# schematic.net
KiCad netlist of a schematic drawn in EasyEDA
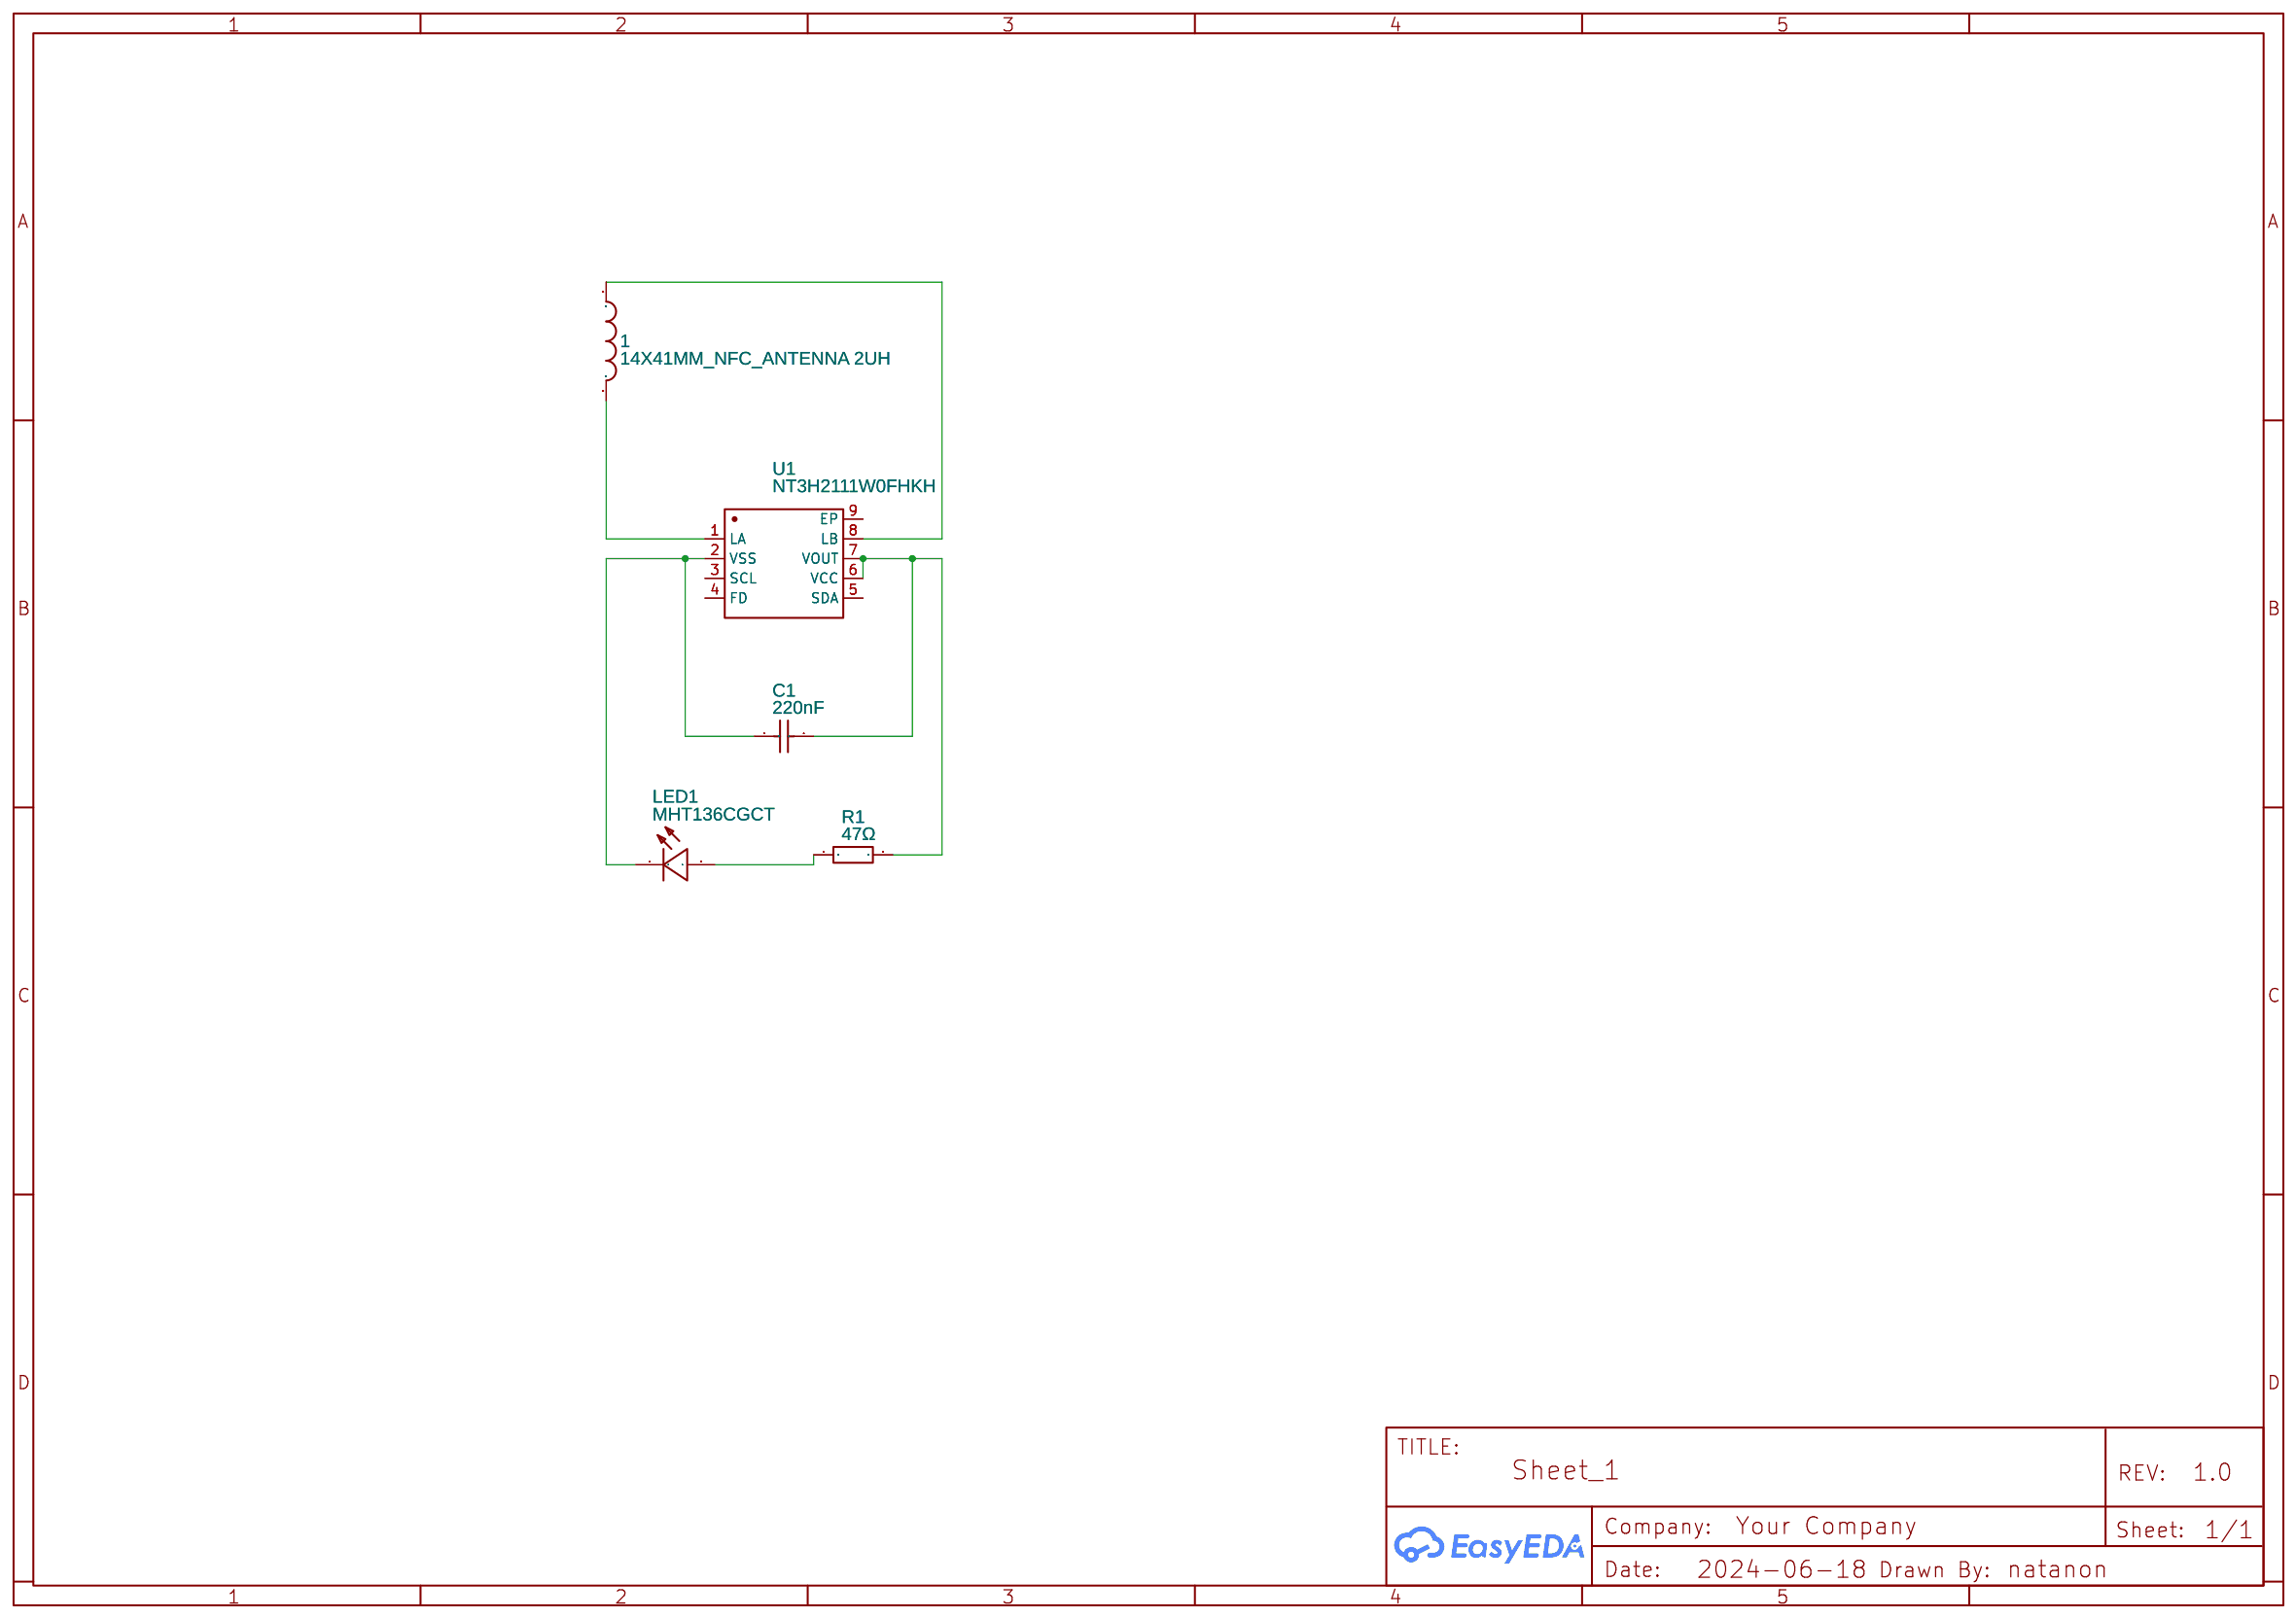
[diagram p0: schematic sheet]

(export (version "E")
  (design (tool "Eeschema 10.0.6"))
  (components
    (comp (ref "1") (value "14X41MM_NFC_ANTENNA 2UH") (libsource (lib "") (part "14X41MM_NFC_ANTENNA 2UH")))
    (comp (ref "C1")
      (value "220nF")
      (fields (field (name "Manufacturer Part") "0603B224K250NT") (field (name "Manufacturer") "FH(风华)"))
      (libsource (lib "") (part "0603B224K250NT"))
    )
    (comp (ref "LED1")
      (value "MHT136CGCT")
      (fields (field (name "Manufacturer") "MEIHUA(美华)"))
      (libsource (lib "") (part "MHT136CGCT"))
    )
    (comp (ref "R1")
      (value "47Ω")
      (fields
        (field (name "Manufacturer Part") "0402WGF470JTCE")
        (field (name "Manufacturer") "UNI-ROYAL(厚声)")
      )
      (libsource (lib "") (part "0402WGF470JTCE"))
    )
    (comp (ref "U1")
      (value "NT3H2111W0FHKH")
      (fields (field (name "Manufacturer") "NXP(恩智浦)"))
      (libsource (lib "") (part "NT3H2111W0FHKH"))
    )
  )
  (nets
    (net (code "1") (name "Net-(LED1-A)") (class "Default")
      (node (ref "LED1") (pin "2") (pinfunction "A_2") (pintype "unspecified"))
      (node (ref "R1") (pin "1") (pinfunction "1_1") (pintype "input"))
    )
    (net (code "2") (name "Net-(LED1-K)") (class "Default")
      (node (ref "C1") (pin "1") (pinfunction "1_1") (pintype "input"))
      (node (ref "LED1") (pin "1") (pinfunction "K_1") (pintype "unspecified"))
      (node (ref "U1") (pin "2") (pinfunction "VSS_2") (pintype "unspecified"))
    )
    (net (code "3") (name "Net-(U1-LA)") (class "Default")
      (node (ref "1") (pin "P$2") (pinfunction "P$2_P$2") (pintype "bidirectional"))
      (node (ref "U1") (pin "1") (pinfunction "LA_1") (pintype "unspecified"))
    )
    (net (code "4") (name "Net-(U1-LB)") (class "Default")
      (node (ref "1") (pin "P$1") (pinfunction "P$1_P$1") (pintype "bidirectional"))
      (node (ref "U1") (pin "8") (pinfunction "LB_8") (pintype "unspecified"))
    )
    (net (code "5") (name "Net-(U1-VCC)") (class "Default")
      (node (ref "C1") (pin "2") (pinfunction "2_2") (pintype "input"))
      (node (ref "R1") (pin "2") (pinfunction "2_2") (pintype "input"))
      (node (ref "U1") (pin "6") (pinfunction "VCC_6") (pintype "unspecified"))
      (node (ref "U1") (pin "7") (pinfunction "VOUT_7") (pintype "unspecified"))
    )
    (net (code "6") (name "unconnected-(U1-EP-Pad9)") (class "Default")
      (node (ref "U1") (pin "9") (pinfunction "EP_9") (pintype "unspecified"))
    )
    (net (code "7") (name "unconnected-(U1-FD-Pad4)") (class "Default")
      (node (ref "U1") (pin "4") (pinfunction "FD_4") (pintype "unspecified"))
    )
    (net (code "8") (name "unconnected-(U1-SCL-Pad3)") (class "Default")
      (node (ref "U1") (pin "3") (pinfunction "SCL_3") (pintype "unspecified"))
    )
    (net (code "9") (name "unconnected-(U1-SDA-Pad5)") (class "Default")
      (node (ref "U1") (pin "5") (pinfunction "SDA_5") (pintype "unspecified"))
    )
  )
)
